# Rect.net
KiCad netlist of a schematic drawn in Altium Designer
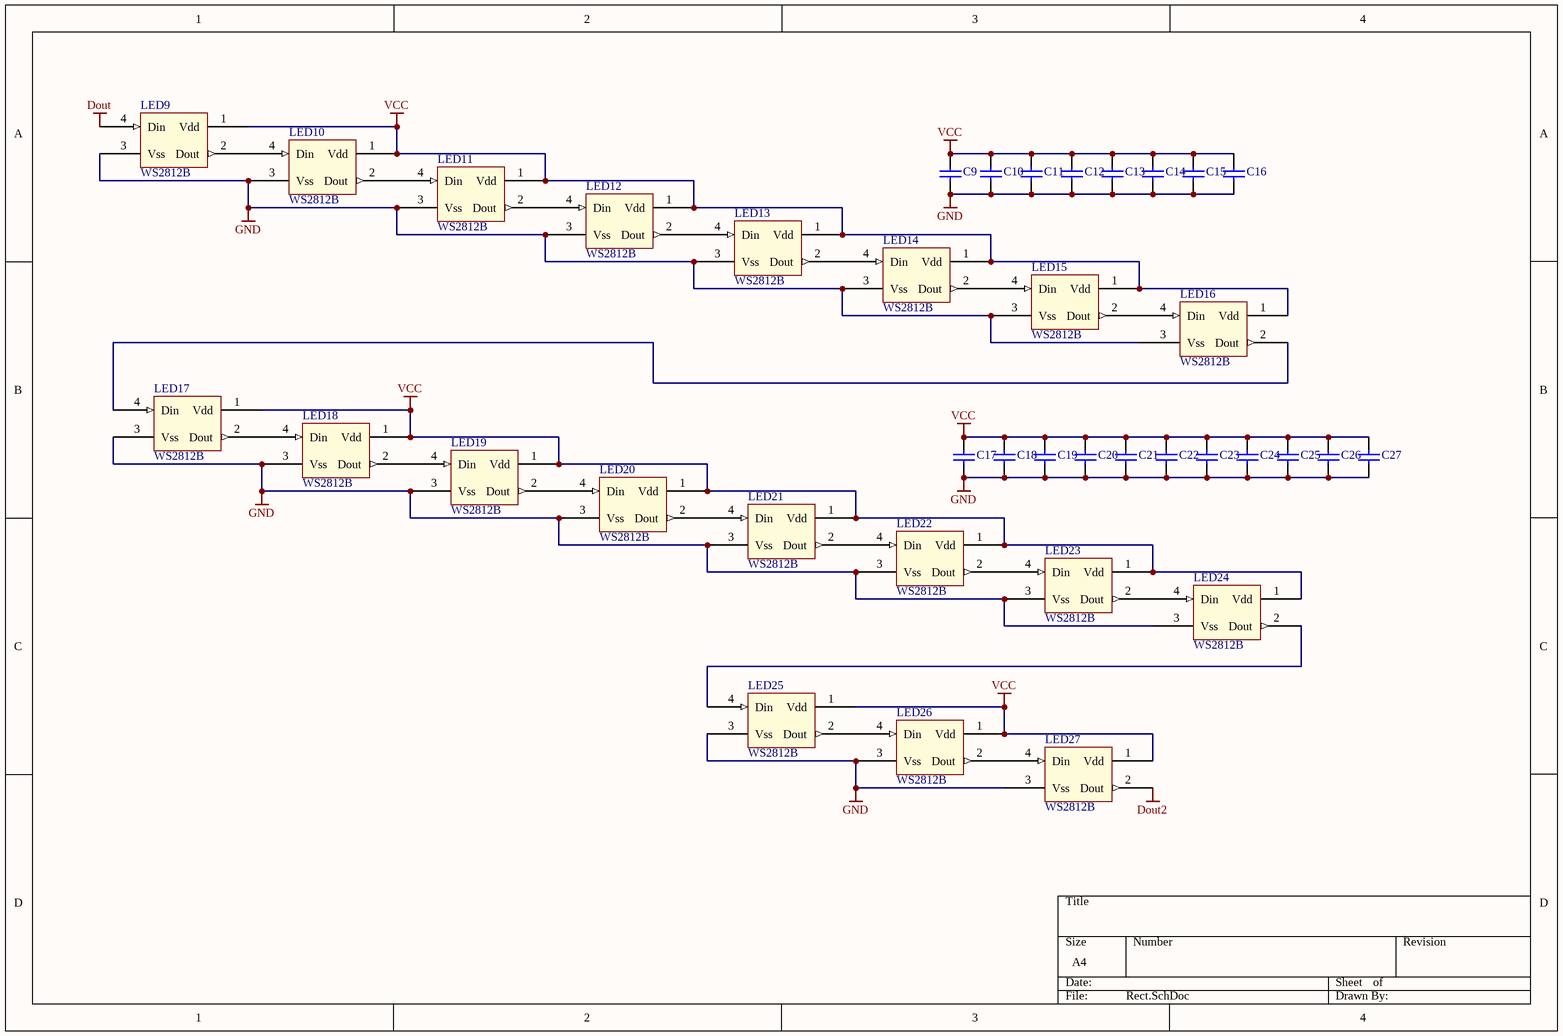
[diagram p0: Rect.SchDoc]

(export (version "E")
  (design (tool "Eeschema 10.0.6"))
  (components
    (comp (ref "C9")
      (value "~")
      (footprint "C1206")
      (description "Capacitor")
      (fields (field (name "PUBLISHER") "Altium Limited"))
      (libsource (lib "Miscellaneous Devices") (part "Cap"))
    )
    (comp (ref "C10")
      (value "~")
      (footprint "C1206")
      (description "Capacitor")
      (fields (field (name "PUBLISHER") "Altium Limited"))
      (libsource (lib "Miscellaneous Devices") (part "Cap"))
    )
    (comp (ref "C11")
      (value "~")
      (footprint "C1206")
      (description "Capacitor")
      (fields (field (name "PUBLISHER") "Altium Limited"))
      (libsource (lib "Miscellaneous Devices") (part "Cap"))
    )
    (comp (ref "C12")
      (value "~")
      (footprint "C1206")
      (description "Capacitor")
      (fields (field (name "PUBLISHER") "Altium Limited"))
      (libsource (lib "Miscellaneous Devices") (part "Cap"))
    )
    (comp (ref "C13")
      (value "~")
      (footprint "C1206")
      (description "Capacitor")
      (fields (field (name "PUBLISHER") "Altium Limited"))
      (libsource (lib "Miscellaneous Devices") (part "Cap"))
    )
    (comp (ref "C14")
      (value "~")
      (footprint "C1206")
      (description "Capacitor")
      (fields (field (name "PUBLISHER") "Altium Limited"))
      (libsource (lib "Miscellaneous Devices") (part "Cap"))
    )
    (comp (ref "C15")
      (value "~")
      (footprint "C1206")
      (description "Capacitor")
      (fields (field (name "PUBLISHER") "Altium Limited"))
      (libsource (lib "Miscellaneous Devices") (part "Cap"))
    )
    (comp (ref "C16")
      (value "~")
      (footprint "C1206")
      (description "Capacitor")
      (fields (field (name "PUBLISHER") "Altium Limited"))
      (libsource (lib "Miscellaneous Devices") (part "Cap"))
    )
    (comp (ref "C17")
      (value "~")
      (footprint "C1206")
      (description "Capacitor")
      (fields (field (name "PUBLISHER") "Altium Limited"))
      (libsource (lib "Miscellaneous Devices") (part "Cap"))
    )
    (comp (ref "C18")
      (value "~")
      (footprint "C1206")
      (description "Capacitor")
      (fields (field (name "PUBLISHER") "Altium Limited"))
      (libsource (lib "Miscellaneous Devices") (part "Cap"))
    )
    (comp (ref "C19")
      (value "~")
      (footprint "C1206")
      (description "Capacitor")
      (fields (field (name "PUBLISHER") "Altium Limited"))
      (libsource (lib "Miscellaneous Devices") (part "Cap"))
    )
    (comp (ref "C20")
      (value "~")
      (footprint "C1206")
      (description "Capacitor")
      (fields (field (name "PUBLISHER") "Altium Limited"))
      (libsource (lib "Miscellaneous Devices") (part "Cap"))
    )
    (comp (ref "C21")
      (value "~")
      (footprint "C1206")
      (description "Capacitor")
      (fields (field (name "PUBLISHER") "Altium Limited"))
      (libsource (lib "Miscellaneous Devices") (part "Cap"))
    )
    (comp (ref "C22")
      (value "~")
      (footprint "C1206")
      (description "Capacitor")
      (fields (field (name "PUBLISHER") "Altium Limited"))
      (libsource (lib "Miscellaneous Devices") (part "Cap"))
    )
    (comp (ref "C23")
      (value "~")
      (footprint "C1206")
      (description "Capacitor")
      (fields (field (name "PUBLISHER") "Altium Limited"))
      (libsource (lib "Miscellaneous Devices") (part "Cap"))
    )
    (comp (ref "C24")
      (value "~")
      (footprint "C1206")
      (description "Capacitor")
      (fields (field (name "PUBLISHER") "Altium Limited"))
      (libsource (lib "Miscellaneous Devices") (part "Cap"))
    )
    (comp (ref "C25")
      (value "~")
      (footprint "C1206")
      (description "Capacitor")
      (fields (field (name "PUBLISHER") "Altium Limited"))
      (libsource (lib "Miscellaneous Devices") (part "Cap"))
    )
    (comp (ref "C26")
      (value "~")
      (footprint "C1206")
      (description "Capacitor")
      (fields (field (name "PUBLISHER") "Altium Limited"))
      (libsource (lib "Miscellaneous Devices") (part "Cap"))
    )
    (comp (ref "C27")
      (value "~")
      (footprint "C1206")
      (description "Capacitor")
      (fields (field (name "PUBLISHER") "Altium Limited"))
      (libsource (lib "Miscellaneous Devices") (part "Cap"))
    )
    (comp (ref "LED9") (value "WS2812B") (footprint "WS2812B") (libsource (lib "WS2812") (part "WS2812B")))
    (comp (ref "LED10") (value "WS2812B") (footprint "WS2812B") (libsource (lib "WS2812") (part "WS2812B")))
    (comp (ref "LED11") (value "WS2812B") (footprint "WS2812B") (libsource (lib "WS2812") (part "WS2812B")))
    (comp (ref "LED12") (value "WS2812B") (footprint "WS2812B") (libsource (lib "WS2812") (part "WS2812B")))
    (comp (ref "LED13") (value "WS2812B") (footprint "WS2812B") (libsource (lib "WS2812") (part "WS2812B")))
    (comp (ref "LED14") (value "WS2812B") (footprint "WS2812B") (libsource (lib "WS2812") (part "WS2812B")))
    (comp (ref "LED15") (value "WS2812B") (footprint "WS2812B") (libsource (lib "WS2812") (part "WS2812B")))
    (comp (ref "LED16") (value "WS2812B") (footprint "WS2812B") (libsource (lib "WS2812") (part "WS2812B")))
    (comp (ref "LED17") (value "WS2812B") (footprint "WS2812B") (libsource (lib "WS2812") (part "WS2812B")))
    (comp (ref "LED18") (value "WS2812B") (footprint "WS2812B") (libsource (lib "WS2812") (part "WS2812B")))
    (comp (ref "LED19") (value "WS2812B") (footprint "WS2812B") (libsource (lib "WS2812") (part "WS2812B")))
    (comp (ref "LED20") (value "WS2812B") (footprint "WS2812B") (libsource (lib "WS2812") (part "WS2812B")))
    (comp (ref "LED21") (value "WS2812B") (footprint "WS2812B") (libsource (lib "WS2812") (part "WS2812B")))
    (comp (ref "LED22") (value "WS2812B") (footprint "WS2812B") (libsource (lib "WS2812") (part "WS2812B")))
    (comp (ref "LED23") (value "WS2812B") (footprint "WS2812B") (libsource (lib "WS2812") (part "WS2812B")))
    (comp (ref "LED24") (value "WS2812B") (footprint "WS2812B") (libsource (lib "WS2812") (part "WS2812B")))
    (comp (ref "LED25") (value "WS2812B") (footprint "WS2812B") (libsource (lib "WS2812") (part "WS2812B")))
    (comp (ref "LED26") (value "WS2812B") (footprint "WS2812B") (libsource (lib "WS2812") (part "WS2812B")))
    (comp (ref "LED27") (value "WS2812B") (footprint "WS2812B") (libsource (lib "WS2812") (part "WS2812B")))
  )
  (nets
    (net (code "1") (name "Dout") (class "Default")
      (node (ref "LED9") (pin "4") (pinfunction "Din_4") (pintype "input"))
    )
    (net (code "2") (name "Dout2") (class "Default")
      (node (ref "LED27") (pin "2") (pinfunction "Dout_2") (pintype "output"))
    )
    (net (code "3") (name "GND") (class "Default")
      (node (ref "C10") (pin "1") (pinfunction "1_1") (pintype "passive"))
      (node (ref "C11") (pin "1") (pinfunction "1_1") (pintype "passive"))
      (node (ref "C12") (pin "1") (pinfunction "1_1") (pintype "passive"))
      (node (ref "C13") (pin "1") (pinfunction "1_1") (pintype "passive"))
      (node (ref "C14") (pin "1") (pinfunction "1_1") (pintype "passive"))
      (node (ref "C15") (pin "1") (pinfunction "1_1") (pintype "passive"))
      (node (ref "C16") (pin "1") (pinfunction "1_1") (pintype "passive"))
      (node (ref "C17") (pin "1") (pinfunction "1_1") (pintype "passive"))
      (node (ref "C18") (pin "1") (pinfunction "1_1") (pintype "passive"))
      (node (ref "C19") (pin "1") (pinfunction "1_1") (pintype "passive"))
      (node (ref "C20") (pin "1") (pinfunction "1_1") (pintype "passive"))
      (node (ref "C21") (pin "1") (pinfunction "1_1") (pintype "passive"))
      (node (ref "C22") (pin "1") (pinfunction "1_1") (pintype "passive"))
      (node (ref "C23") (pin "1") (pinfunction "1_1") (pintype "passive"))
      (node (ref "C24") (pin "1") (pinfunction "1_1") (pintype "passive"))
      (node (ref "C25") (pin "1") (pinfunction "1_1") (pintype "passive"))
      (node (ref "C26") (pin "1") (pinfunction "1_1") (pintype "passive"))
      (node (ref "C27") (pin "1") (pinfunction "1_1") (pintype "passive"))
      (node (ref "C9") (pin "1") (pinfunction "1_1") (pintype "passive"))
      (node (ref "LED10") (pin "3") (pinfunction "Vss_3") (pintype "power_in"))
      (node (ref "LED11") (pin "3") (pinfunction "Vss_3") (pintype "power_in"))
      (node (ref "LED12") (pin "3") (pinfunction "Vss_3") (pintype "power_in"))
      (node (ref "LED13") (pin "3") (pinfunction "Vss_3") (pintype "power_in"))
      (node (ref "LED14") (pin "3") (pinfunction "Vss_3") (pintype "power_in"))
      (node (ref "LED15") (pin "3") (pinfunction "Vss_3") (pintype "power_in"))
      (node (ref "LED16") (pin "3") (pinfunction "Vss_3") (pintype "power_in"))
      (node (ref "LED17") (pin "3") (pinfunction "Vss_3") (pintype "power_in"))
      (node (ref "LED18") (pin "3") (pinfunction "Vss_3") (pintype "power_in"))
      (node (ref "LED19") (pin "3") (pinfunction "Vss_3") (pintype "power_in"))
      (node (ref "LED20") (pin "3") (pinfunction "Vss_3") (pintype "power_in"))
      (node (ref "LED21") (pin "3") (pinfunction "Vss_3") (pintype "power_in"))
      (node (ref "LED22") (pin "3") (pinfunction "Vss_3") (pintype "power_in"))
      (node (ref "LED23") (pin "3") (pinfunction "Vss_3") (pintype "power_in"))
      (node (ref "LED24") (pin "3") (pinfunction "Vss_3") (pintype "power_in"))
      (node (ref "LED25") (pin "3") (pinfunction "Vss_3") (pintype "power_in"))
      (node (ref "LED26") (pin "3") (pinfunction "Vss_3") (pintype "power_in"))
      (node (ref "LED27") (pin "3") (pinfunction "Vss_3") (pintype "power_in"))
      (node (ref "LED9") (pin "3") (pinfunction "Vss_3") (pintype "power_in"))
    )
    (net (code "4") (name "Net-(LED10-Din)") (class "Default")
      (node (ref "LED10") (pin "4") (pinfunction "Din_4") (pintype "input"))
      (node (ref "LED9") (pin "2") (pinfunction "Dout_2") (pintype "output"))
    )
    (net (code "5") (name "Net-(LED10-Dout)") (class "Default")
      (node (ref "LED10") (pin "2") (pinfunction "Dout_2") (pintype "output"))
      (node (ref "LED11") (pin "4") (pinfunction "Din_4") (pintype "input"))
    )
    (net (code "6") (name "Net-(LED11-Dout)") (class "Default")
      (node (ref "LED11") (pin "2") (pinfunction "Dout_2") (pintype "output"))
      (node (ref "LED12") (pin "4") (pinfunction "Din_4") (pintype "input"))
    )
    (net (code "7") (name "Net-(LED12-Dout)") (class "Default")
      (node (ref "LED12") (pin "2") (pinfunction "Dout_2") (pintype "output"))
      (node (ref "LED13") (pin "4") (pinfunction "Din_4") (pintype "input"))
    )
    (net (code "8") (name "Net-(LED13-Dout)") (class "Default")
      (node (ref "LED13") (pin "2") (pinfunction "Dout_2") (pintype "output"))
      (node (ref "LED14") (pin "4") (pinfunction "Din_4") (pintype "input"))
    )
    (net (code "9") (name "Net-(LED14-Dout)") (class "Default")
      (node (ref "LED14") (pin "2") (pinfunction "Dout_2") (pintype "output"))
      (node (ref "LED15") (pin "4") (pinfunction "Din_4") (pintype "input"))
    )
    (net (code "10") (name "Net-(LED15-Dout)") (class "Default")
      (node (ref "LED15") (pin "2") (pinfunction "Dout_2") (pintype "output"))
      (node (ref "LED16") (pin "4") (pinfunction "Din_4") (pintype "input"))
    )
    (net (code "11") (name "Net-(LED16-Dout)") (class "Default")
      (node (ref "LED16") (pin "2") (pinfunction "Dout_2") (pintype "output"))
      (node (ref "LED17") (pin "4") (pinfunction "Din_4") (pintype "input"))
    )
    (net (code "12") (name "Net-(LED17-Dout)") (class "Default")
      (node (ref "LED17") (pin "2") (pinfunction "Dout_2") (pintype "output"))
      (node (ref "LED18") (pin "4") (pinfunction "Din_4") (pintype "input"))
    )
    (net (code "13") (name "Net-(LED18-Dout)") (class "Default")
      (node (ref "LED18") (pin "2") (pinfunction "Dout_2") (pintype "output"))
      (node (ref "LED19") (pin "4") (pinfunction "Din_4") (pintype "input"))
    )
    (net (code "14") (name "Net-(LED19-Dout)") (class "Default")
      (node (ref "LED19") (pin "2") (pinfunction "Dout_2") (pintype "output"))
      (node (ref "LED20") (pin "4") (pinfunction "Din_4") (pintype "input"))
    )
    (net (code "15") (name "Net-(LED20-Dout)") (class "Default")
      (node (ref "LED20") (pin "2") (pinfunction "Dout_2") (pintype "output"))
      (node (ref "LED21") (pin "4") (pinfunction "Din_4") (pintype "input"))
    )
    (net (code "16") (name "Net-(LED21-Dout)") (class "Default")
      (node (ref "LED21") (pin "2") (pinfunction "Dout_2") (pintype "output"))
      (node (ref "LED22") (pin "4") (pinfunction "Din_4") (pintype "input"))
    )
    (net (code "17") (name "Net-(LED22-Dout)") (class "Default")
      (node (ref "LED22") (pin "2") (pinfunction "Dout_2") (pintype "output"))
      (node (ref "LED23") (pin "4") (pinfunction "Din_4") (pintype "input"))
    )
    (net (code "18") (name "Net-(LED23-Dout)") (class "Default")
      (node (ref "LED23") (pin "2") (pinfunction "Dout_2") (pintype "output"))
      (node (ref "LED24") (pin "4") (pinfunction "Din_4") (pintype "input"))
    )
    (net (code "19") (name "Net-(LED24-Dout)") (class "Default")
      (node (ref "LED24") (pin "2") (pinfunction "Dout_2") (pintype "output"))
      (node (ref "LED25") (pin "4") (pinfunction "Din_4") (pintype "input"))
    )
    (net (code "20") (name "Net-(LED25-Dout)") (class "Default")
      (node (ref "LED25") (pin "2") (pinfunction "Dout_2") (pintype "output"))
      (node (ref "LED26") (pin "4") (pinfunction "Din_4") (pintype "input"))
    )
    (net (code "21") (name "Net-(LED26-Dout)") (class "Default")
      (node (ref "LED26") (pin "2") (pinfunction "Dout_2") (pintype "output"))
      (node (ref "LED27") (pin "4") (pinfunction "Din_4") (pintype "input"))
    )
    (net (code "22") (name "VCC") (class "Default")
      (node (ref "C10") (pin "2") (pinfunction "2_2") (pintype "passive"))
      (node (ref "C11") (pin "2") (pinfunction "2_2") (pintype "passive"))
      (node (ref "C12") (pin "2") (pinfunction "2_2") (pintype "passive"))
      (node (ref "C13") (pin "2") (pinfunction "2_2") (pintype "passive"))
      (node (ref "C14") (pin "2") (pinfunction "2_2") (pintype "passive"))
      (node (ref "C15") (pin "2") (pinfunction "2_2") (pintype "passive"))
      (node (ref "C16") (pin "2") (pinfunction "2_2") (pintype "passive"))
      (node (ref "C17") (pin "2") (pinfunction "2_2") (pintype "passive"))
      (node (ref "C18") (pin "2") (pinfunction "2_2") (pintype "passive"))
      (node (ref "C19") (pin "2") (pinfunction "2_2") (pintype "passive"))
      (node (ref "C20") (pin "2") (pinfunction "2_2") (pintype "passive"))
      (node (ref "C21") (pin "2") (pinfunction "2_2") (pintype "passive"))
      (node (ref "C22") (pin "2") (pinfunction "2_2") (pintype "passive"))
      (node (ref "C23") (pin "2") (pinfunction "2_2") (pintype "passive"))
      (node (ref "C24") (pin "2") (pinfunction "2_2") (pintype "passive"))
      (node (ref "C25") (pin "2") (pinfunction "2_2") (pintype "passive"))
      (node (ref "C26") (pin "2") (pinfunction "2_2") (pintype "passive"))
      (node (ref "C27") (pin "2") (pinfunction "2_2") (pintype "passive"))
      (node (ref "C9") (pin "2") (pinfunction "2_2") (pintype "passive"))
      (node (ref "LED10") (pin "1") (pinfunction "Vdd_1") (pintype "power_in"))
      (node (ref "LED11") (pin "1") (pinfunction "Vdd_1") (pintype "power_in"))
      (node (ref "LED12") (pin "1") (pinfunction "Vdd_1") (pintype "power_in"))
      (node (ref "LED13") (pin "1") (pinfunction "Vdd_1") (pintype "power_in"))
      (node (ref "LED14") (pin "1") (pinfunction "Vdd_1") (pintype "power_in"))
      (node (ref "LED15") (pin "1") (pinfunction "Vdd_1") (pintype "power_in"))
      (node (ref "LED16") (pin "1") (pinfunction "Vdd_1") (pintype "power_in"))
      (node (ref "LED17") (pin "1") (pinfunction "Vdd_1") (pintype "power_in"))
      (node (ref "LED18") (pin "1") (pinfunction "Vdd_1") (pintype "power_in"))
      (node (ref "LED19") (pin "1") (pinfunction "Vdd_1") (pintype "power_in"))
      (node (ref "LED20") (pin "1") (pinfunction "Vdd_1") (pintype "power_in"))
      (node (ref "LED21") (pin "1") (pinfunction "Vdd_1") (pintype "power_in"))
      (node (ref "LED22") (pin "1") (pinfunction "Vdd_1") (pintype "power_in"))
      (node (ref "LED23") (pin "1") (pinfunction "Vdd_1") (pintype "power_in"))
      (node (ref "LED24") (pin "1") (pinfunction "Vdd_1") (pintype "power_in"))
      (node (ref "LED25") (pin "1") (pinfunction "Vdd_1") (pintype "power_in"))
      (node (ref "LED26") (pin "1") (pinfunction "Vdd_1") (pintype "power_in"))
      (node (ref "LED27") (pin "1") (pinfunction "Vdd_1") (pintype "power_in"))
      (node (ref "LED9") (pin "1") (pinfunction "Vdd_1") (pintype "power_in"))
    )
  )
)
